# CH32X033F-R0.net
KiCad netlist of a schematic drawn in Altium Designer
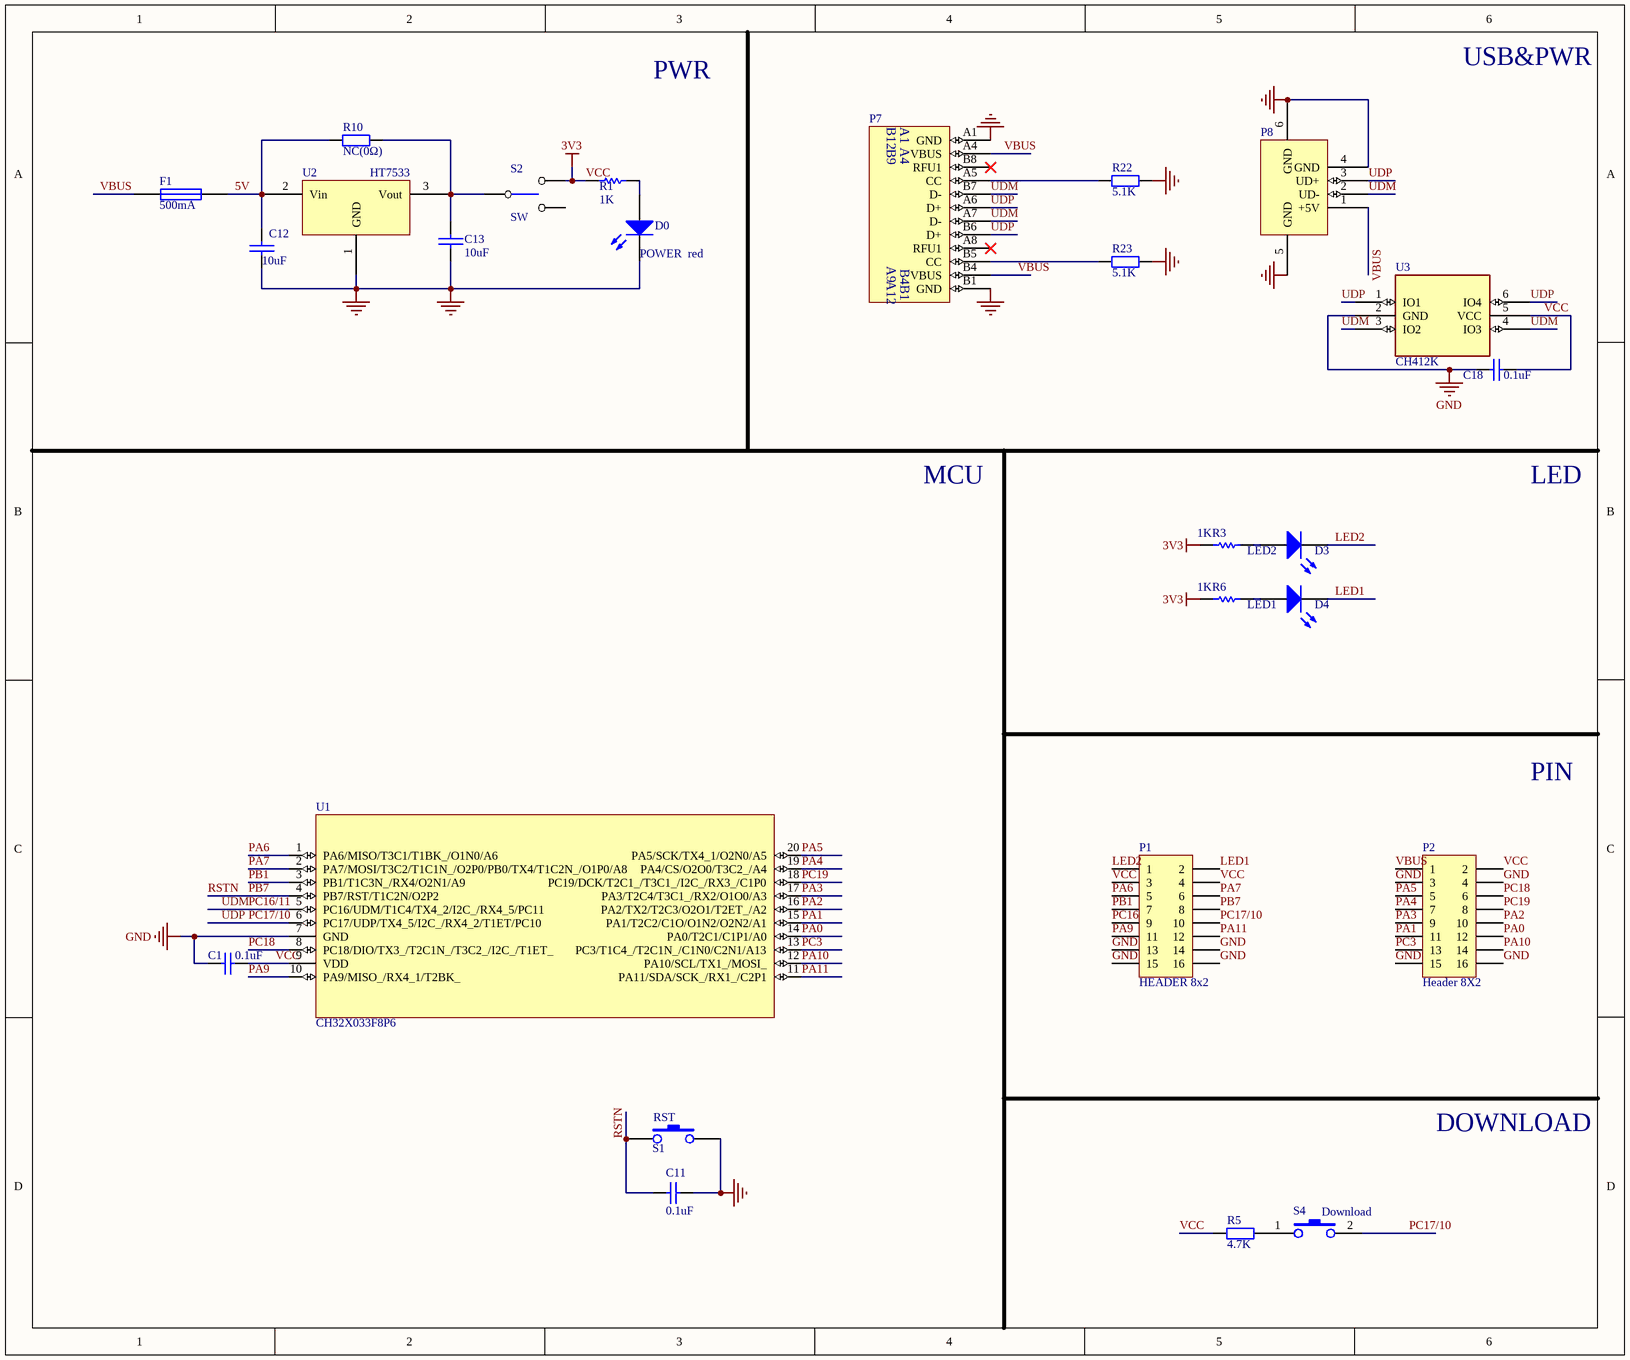
[diagram p0: CH32X033F-R0.SchDoc]

(export (version "E")
  (design (tool "Eeschema 10.0.6"))
  (components
    (comp (ref "C1")
      (value "0.1uF")
      (footprint "0603_C")
      (description "Capacitor")
      (libsource (lib "Miscellaneous Devices") (part "Cap"))
    )
    (comp (ref "C11")
      (value "0.1uF")
      (footprint "0603_C")
      (description "Capacitor")
      (libsource (lib "*") (part "Cap"))
    )
    (comp (ref "C12")
      (value "10uF")
      (footprint "0603_C")
      (description "Capacitor")
      (libsource (lib "*") (part "CAP"))
    )
    (comp (ref "C13")
      (value "10uF")
      (footprint "0603_C")
      (description "Capacitor")
      (libsource (lib "*") (part "CAP"))
    )
    (comp (ref "C18")
      (value "0.1uF")
      (footprint "0603_C")
      (description "Capacitor")
      (libsource (lib "Miscellaneous Devices") (part "Cap"))
    )
    (comp (ref "D0")
      (value "POWER  red")
      (footprint "0603+")
      (description "Typical INFRARED GaAs LED")
      (fields (field (name "PUBLISHER") "Altium Limited"))
      (libsource (lib "*") (part "LED0"))
    )
    (comp (ref "D3")
      (value "LED2")
      (footprint "0603+")
      (description "Typical INFRARED GaAs LED")
      (fields (field (name "PUBLISHER") "Altium Limited"))
      (libsource (lib "*") (part "LED0"))
    )
    (comp (ref "D4")
      (value "LED1")
      (footprint "0603+")
      (description "Typical INFRARED GaAs LED")
      (fields (field (name "PUBLISHER") "Altium Limited"))
      (libsource (lib "*") (part "LED0"))
    )
    (comp (ref "F1")
      (value "500mA")
      (footprint "0603")
      (description "Fuse")
      (libsource (lib "*") (part "FUSE1"))
    )
    (comp (ref "P1")
      (value "HEADER 8x2")
      (footprint "MYPCB:IDC16-2.54mm")
      (description "Header, 8-Pin, Dual row")
      (libsource (lib "wch_sch_others") (part "HEADER 8x2"))
    )
    (comp (ref "P2")
      (value "Header 8X2")
      (footprint "IDC16-2.54mm")
      (description "Header, 8-Pin, Dual row")
      (fields (field (name "PUBLISHER") "Altium Limited"))
      (libsource (lib "Miscellaneous Connectors") (part "Header 8X2"))
    )
    (comp (ref "P7")
      (value "TYPE-C")
      (footprint "TYPE-C-Receptacle-2.0")
      (libsource (lib "*") (part "TYPE-C1"))
    )
    (comp (ref "P8")
      (value "USB_A")
      (footprint "USBAF")
      (description "USB Port")
      (libsource (lib "*") (part "USB"))
    )
    (comp (ref "R1")
      (value "1K")
      (footprint "0603")
      (description "Semiconductor Resistor")
      (libsource (lib "*") (part "Res Semi"))
    )
    (comp (ref "R3")
      (value "1K")
      (footprint "0603")
      (description "Semiconductor Resistor")
      (libsource (lib "*") (part "Res Semi"))
    )
    (comp (ref "R5")
      (value "4.7K")
      (footprint "0603")
      (description "Resistor")
      (libsource (lib "Miscellaneous Devices") (part "Res2"))
    )
    (comp (ref "R6")
      (value "1K")
      (footprint "0603")
      (description "Semiconductor Resistor")
      (libsource (lib "*") (part "Res Semi"))
    )
    (comp (ref "R10")
      (value "NC(0Ω)")
      (footprint "0603")
      (description "Resistor")
      (libsource (lib "*") (part "Res2"))
    )
    (comp (ref "R22")
      (value "5.1K")
      (footprint "0603")
      (description "Resistor")
      (libsource (lib "Miscellaneous Devices") (part "Res2"))
    )
    (comp (ref "R23")
      (value "5.1K")
      (footprint "0603")
      (description "Resistor")
      (libsource (lib "Miscellaneous Devices") (part "Res2"))
    )
    (comp (ref "S1") (value "RST") (footprint "SMD_6.1x3.65x2.5mm-KEY") (libsource (lib "*") (part "KEY")))
    (comp (ref "S2") (value "SW") (footprint "SW1") (libsource (lib "*") (part "SW")))
    (comp (ref "S4")
      (value "Download")
      (footprint "SMD_6.1x3.65x2.5mm-KEY")
      (libsource (lib "wch_sch_others") (part "KEY1"))
    )
    (comp (ref "U1")
      (value "CH32X033F8P6")
      (footprint "TSSOP20")
      (description "RISC-V MCU with USB/ADC/SPI/I2C/UART*4/OA*2/CMP*2")
      (libsource (lib "CHXXX") (part "CH32X033F8P6"))
    )
    (comp (ref "U2")
      (value "HT7533")
      (footprint "SOT-89")
      (libsource (lib "wch_sch_others") (part "1117-3.3V"))
    )
    (comp (ref "U3")
      (value "CH412K")
      (footprint "SOT-363")
      (description "Qaud ESD protect, high speed")
      (libsource (lib "CHXXX") (part "CH412K"))
    )
  )
  (nets
    (net (code "1") (name "/5V") (class "Default")
      (node (ref "C12") (pin "1") (pinfunction "1_1") (pintype "passive"))
      (node (ref "F1") (pin "2") (pinfunction "2_2") (pintype "passive"))
      (node (ref "R10") (pin "2") (pinfunction "2_2") (pintype "passive"))
      (node (ref "U2") (pin "2") (pinfunction "Vin_2") (pintype "passive"))
    )
    (net (code "3") (name "/LED1") (class "Default")
      (node (ref "D4") (pin "2") (pinfunction "K_2") (pintype "passive"))
      (node (ref "P1") (pin "2") (pinfunction "2_2") (pintype "passive"))
    )
    (net (code "4") (name "/LED2") (class "Default")
      (node (ref "D3") (pin "2") (pinfunction "K_2") (pintype "passive"))
      (node (ref "P1") (pin "1") (pinfunction "1_1") (pintype "passive"))
    )
    (net (code "5") (name "/PA0") (class "Default")
      (node (ref "P2") (pin "12") (pinfunction "12_12") (pintype "passive"))
      (node (ref "U1") (pin "14") (pinfunction "PA0/T2C1/C1P1/A0_14") (pintype "bidirectional"))
    )
    (net (code "6") (name "/PA1") (class "Default")
      (node (ref "P2") (pin "11") (pinfunction "11_11") (pintype "passive"))
      (node (ref "U1") (pin "15") (pinfunction "PA1/T2C2/C1O/O1N2/O2N2/A1_15") (pintype "bidirectional"))
    )
    (net (code "7") (name "/PA2") (class "Default")
      (node (ref "P2") (pin "10") (pinfunction "10_10") (pintype "passive"))
      (node (ref "U1") (pin "16") (pinfunction "PA2/TX2/T2C3/O2O1/T2ET_/A2_16") (pintype "bidirectional"))
    )
    (net (code "8") (name "/PA3") (class "Default")
      (node (ref "P2") (pin "9") (pinfunction "9_9") (pintype "passive"))
      (node (ref "U1") (pin "17") (pinfunction "PA3/T2C4/T3C1_/RX2/O1O0/A3_17") (pintype "bidirectional"))
    )
    (net (code "9") (name "/PA4") (class "Default")
      (node (ref "P2") (pin "7") (pinfunction "7_7") (pintype "passive"))
      (node (ref "U1") (pin "19") (pinfunction "PA4/CS/O2O0/T3C2_/A4_19") (pintype "bidirectional"))
    )
    (net (code "10") (name "/PA5") (class "Default")
      (node (ref "P2") (pin "5") (pinfunction "5_5") (pintype "passive"))
      (node (ref "U1") (pin "20") (pinfunction "PA5/SCK/TX4_1/O2N0/A5_20") (pintype "bidirectional"))
    )
    (net (code "11") (name "/PA6") (class "Default")
      (node (ref "P1") (pin "5") (pinfunction "5_5") (pintype "passive"))
      (node (ref "U1") (pin "1") (pinfunction "PA6/MISO/T3C1/T1BK_/O1N0/A6_1") (pintype "bidirectional"))
    )
    (net (code "12") (name "/PA7") (class "Default")
      (node (ref "P1") (pin "6") (pinfunction "6_6") (pintype "passive"))
      (node (ref "U1") (pin "2") (pinfunction "PA7/MOSI/T3C2/T1C1N_/O2P0/PB0/TX4/T1C2N_/O1P0/A8_2") (pintype "bidirectional"))
    )
    (net (code "13") (name "/PA9") (class "Default")
      (node (ref "P1") (pin "11") (pinfunction "11_11") (pintype "passive"))
      (node (ref "U1") (pin "10") (pinfunction "PA9/MISO_/RX4_1/T2BK__10") (pintype "bidirectional"))
    )
    (net (code "14") (name "/PA10") (class "Default")
      (node (ref "P2") (pin "14") (pinfunction "14_14") (pintype "passive"))
      (node (ref "U1") (pin "12") (pinfunction "PA10/SCL/TX1_/MOSI__12") (pintype "bidirectional"))
    )
    (net (code "15") (name "/PA11") (class "Default")
      (node (ref "P1") (pin "12") (pinfunction "12_12") (pintype "passive"))
      (node (ref "U1") (pin "11") (pinfunction "PA11/SDA/SCK_/RX1_/C2P1_11") (pintype "bidirectional"))
    )
    (net (code "16") (name "/PB1") (class "Default")
      (node (ref "P1") (pin "7") (pinfunction "7_7") (pintype "passive"))
      (node (ref "U1") (pin "3") (pinfunction "PB1/T1C3N_/RX4/O2N1/A9_3") (pintype "bidirectional"))
    )
    (net (code "17") (name "/PB7") (class "Default")
      (node (ref "C11") (pin "2") (pinfunction "2_2") (pintype "passive"))
      (node (ref "P1") (pin "8") (pinfunction "8_8") (pintype "passive"))
      (node (ref "S1") (pin "1") (pinfunction "1_1") (pintype "passive"))
      (node (ref "U1") (pin "4") (pinfunction "PB7/RST/T1C2N/O2P2_4") (pintype "bidirectional"))
    )
    (net (code "18") (name "/PC3") (class "Default")
      (node (ref "P2") (pin "13") (pinfunction "13_13") (pintype "passive"))
      (node (ref "U1") (pin "13") (pinfunction "PC3/T1C4_/T2C1N_/C1N0/C2N1/A13_13") (pintype "bidirectional"))
    )
    (net (code "19") (name "/PC16{slash}11") (class "Default")
      (node (ref "P1") (pin "9") (pinfunction "9_9") (pintype "passive"))
      (node (ref "P7") (pin "A7") (pinfunction "D-_A7") (pintype "bidirectional"))
      (node (ref "P7") (pin "B7") (pinfunction "D-_B7") (pintype "bidirectional"))
      (node (ref "P8") (pin "2") (pinfunction "UD-_2") (pintype "bidirectional"))
      (node (ref "U1") (pin "5") (pinfunction "PC16/UDM/T1C4/TX4_2/I2C_/RX4_5/PC11_5") (pintype "bidirectional"))
      (node (ref "U3") (pin "3") (pinfunction "IO2_3") (pintype "bidirectional"))
      (node (ref "U3") (pin "4") (pinfunction "IO3_4") (pintype "bidirectional"))
    )
    (net (code "20") (name "/PC17{slash}10") (class "Default")
      (node (ref "P1") (pin "10") (pinfunction "10_10") (pintype "passive"))
      (node (ref "P7") (pin "A6") (pinfunction "D+_A6") (pintype "bidirectional"))
      (node (ref "P7") (pin "B6") (pinfunction "D+_B6") (pintype "bidirectional"))
      (node (ref "P8") (pin "3") (pinfunction "UD+_3") (pintype "bidirectional"))
      (node (ref "S4") (pin "2") (pinfunction "2_2") (pintype "passive"))
      (node (ref "U1") (pin "6") (pinfunction "PC17/UDP/TX4_5/I2C_/RX4_2/T1ET/PC10_6") (pintype "bidirectional"))
      (node (ref "U3") (pin "1") (pinfunction "IO1_1") (pintype "bidirectional"))
      (node (ref "U3") (pin "6") (pinfunction "IO4_6") (pintype "bidirectional"))
    )
    (net (code "21") (name "/PC18") (class "Default")
      (node (ref "P2") (pin "6") (pinfunction "6_6") (pintype "passive"))
      (node (ref "U1") (pin "8") (pinfunction "PC18/DIO/TX3_/T2C1N_/T3C2_/I2C_/T1ET__8") (pintype "bidirectional"))
    )
    (net (code "22") (name "/PC19") (class "Default")
      (node (ref "P2") (pin "8") (pinfunction "8_8") (pintype "passive"))
      (node (ref "U1") (pin "18") (pinfunction "PC19/DCK/T2C1_/T3C1_/I2C_/RX3_/C1P0_18") (pintype "bidirectional"))
    )
    (net (code "23") (name "/VBUS") (class "Default")
      (node (ref "F1") (pin "1") (pinfunction "1_1") (pintype "passive"))
      (node (ref "P2") (pin "1") (pinfunction "1_1") (pintype "passive"))
      (node (ref "P7") (pin "A4") (pinfunction "VBUS_A4") (pintype "bidirectional"))
      (node (ref "P7") (pin "B4") (pinfunction "VBUS_B4") (pintype "bidirectional"))
      (node (ref "P8") (pin "1") (pinfunction "+5V_1") (pintype "power_in"))
    )
    (net (code "24") (name "3V3") (class "Default")
      (node (ref "C1") (pin "1") (pinfunction "1_1") (pintype "passive"))
      (node (ref "C18") (pin "2") (pinfunction "2_2") (pintype "passive"))
      (node (ref "P1") (pin "3") (pinfunction "3_3") (pintype "passive"))
      (node (ref "P1") (pin "4") (pinfunction "4_4") (pintype "passive"))
      (node (ref "P2") (pin "2") (pinfunction "2_2") (pintype "passive"))
      (node (ref "R1") (pin "2") (pinfunction "2_2") (pintype "passive"))
      (node (ref "R3") (pin "1") (pinfunction "1_1") (pintype "passive"))
      (node (ref "R5") (pin "1") (pinfunction "1_1") (pintype "passive"))
      (node (ref "R6") (pin "1") (pinfunction "1_1") (pintype "passive"))
      (node (ref "S2") (pin "3") (pinfunction "3_3") (pintype "passive"))
      (node (ref "U1") (pin "9") (pinfunction "VDD_9") (pintype "power_in"))
      (node (ref "U3") (pin "5") (pinfunction "VCC_5") (pintype "power_in"))
    )
    (net (code "25") (name "GND") (class "Default")
      (node (ref "C1") (pin "2") (pinfunction "2_2") (pintype "passive"))
      (node (ref "C11") (pin "1") (pinfunction "1_1") (pintype "passive"))
      (node (ref "C12") (pin "2") (pinfunction "2_2") (pintype "passive"))
      (node (ref "C13") (pin "2") (pinfunction "2_2") (pintype "passive"))
      (node (ref "C18") (pin "1") (pinfunction "1_1") (pintype "passive"))
      (node (ref "D0") (pin "2") (pinfunction "K_2") (pintype "passive"))
      (node (ref "P1") (pin "13") (pinfunction "13_13") (pintype "passive"))
      (node (ref "P1") (pin "14") (pinfunction "14_14") (pintype "passive"))
      (node (ref "P1") (pin "15") (pinfunction "15_15") (pintype "passive"))
      (node (ref "P1") (pin "16") (pinfunction "16_16") (pintype "passive"))
      (node (ref "P2") (pin "15") (pinfunction "15_15") (pintype "passive"))
      (node (ref "P2") (pin "16") (pinfunction "16_16") (pintype "passive"))
      (node (ref "P2") (pin "3") (pinfunction "3_3") (pintype "passive"))
      (node (ref "P2") (pin "4") (pinfunction "4_4") (pintype "passive"))
      (node (ref "P7") (pin "A1") (pinfunction "GND_A1") (pintype "bidirectional"))
      (node (ref "P7") (pin "B1") (pinfunction "GND_B1") (pintype "bidirectional"))
      (node (ref "P8") (pin "4") (pinfunction "GND_4") (pintype "power_in"))
      (node (ref "P8") (pin "5") (pinfunction "GND_5") (pintype "power_in"))
      (node (ref "P8") (pin "6") (pinfunction "GND_6") (pintype "power_in"))
      (node (ref "R22") (pin "2") (pinfunction "2_2") (pintype "passive"))
      (node (ref "R23") (pin "2") (pinfunction "2_2") (pintype "passive"))
      (node (ref "S1") (pin "2") (pinfunction "2_2") (pintype "passive"))
      (node (ref "U1") (pin "7") (pinfunction "GND_7") (pintype "power_in"))
      (node (ref "U2") (pin "1") (pinfunction "GND_1") (pintype "passive"))
      (node (ref "U3") (pin "2") (pinfunction "GND_2") (pintype "power_in"))
    )
    (net (code "26") (name "Net-(D0-A)") (class "Default")
      (node (ref "D0") (pin "1") (pinfunction "A_1") (pintype "passive"))
      (node (ref "R1") (pin "1") (pinfunction "1_1") (pintype "passive"))
    )
    (net (code "27") (name "Net-(D3-A)") (class "Default")
      (node (ref "D3") (pin "1") (pinfunction "A_1") (pintype "passive"))
      (node (ref "R3") (pin "2") (pinfunction "2_2") (pintype "passive"))
    )
    (net (code "28") (name "Net-(D4-A)") (class "Default")
      (node (ref "D4") (pin "1") (pinfunction "A_1") (pintype "passive"))
      (node (ref "R6") (pin "2") (pinfunction "2_2") (pintype "passive"))
    )
    (net (code "29") (name "Net-(P7-CC-PadA5)") (class "Default")
      (node (ref "P7") (pin "A5") (pinfunction "CC_A5") (pintype "bidirectional"))
      (node (ref "R22") (pin "1") (pinfunction "1_1") (pintype "passive"))
    )
    (net (code "30") (name "Net-(P7-CC-PadB5)") (class "Default")
      (node (ref "P7") (pin "B5") (pinfunction "CC_B5") (pintype "bidirectional"))
      (node (ref "R23") (pin "1") (pinfunction "1_1") (pintype "passive"))
    )
    (net (code "31") (name "Net-(R5-Pad2)") (class "Default")
      (node (ref "R5") (pin "2") (pinfunction "2_2") (pintype "passive"))
      (node (ref "S4") (pin "1") (pinfunction "1_1") (pintype "passive"))
    )
    (net (code "32") (name "Net-(U2-Vout)") (class "Default")
      (node (ref "C13") (pin "1") (pinfunction "1_1") (pintype "passive"))
      (node (ref "R10") (pin "1") (pinfunction "1_1") (pintype "passive"))
      (node (ref "S2") (pin "1") (pinfunction "1_1") (pintype "passive"))
      (node (ref "U2") (pin "3") (pinfunction "Vout_3") (pintype "passive"))
    )
    (net (code "33") (name "unconnected-(P7-RFU1-PadA8)") (class "Default")
      (node (ref "P7") (pin "A8") (pinfunction "RFU1_A8") (pintype "bidirectional+no_connect"))
    )
    (net (code "34") (name "unconnected-(P7-RFU1-PadB8)") (class "Default")
      (node (ref "P7") (pin "B8") (pinfunction "RFU1_B8") (pintype "bidirectional+no_connect"))
    )
    (net (code "35") (name "unconnected-(S2-Pad2)") (class "Default")
      (node (ref "S2") (pin "2") (pinfunction "2_2") (pintype "passive"))
    )
  )
)
